# 6pin_bus.net
KiCad netlist of a schematic drawn in EAGLE
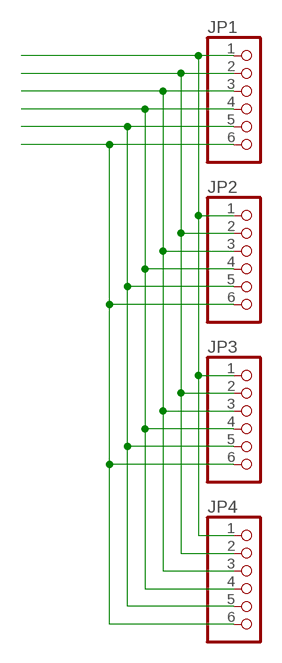
[diagram p0: schematic, sheet 1]

(export (version "E")
  (design (tool "Eeschema 10.0.6"))
  (components
    (comp (ref "JP1")
      (value "PINHD-1X6")
      (footprint "eagle-import:1X06")
      (libsource (lib "eagle-import") (part "PINHD-1X6"))
    )
    (comp (ref "JP2")
      (value "PINHD-1X6")
      (footprint "eagle-import:1X06")
      (libsource (lib "eagle-import") (part "PINHD-1X6"))
    )
    (comp (ref "JP3")
      (value "PINHD-1X6")
      (footprint "eagle-import:1X06")
      (libsource (lib "eagle-import") (part "PINHD-1X6"))
    )
    (comp (ref "JP4")
      (value "PINHD-1X6")
      (footprint "eagle-import:1X06")
      (libsource (lib "eagle-import") (part "PINHD-1X6"))
    )
  )
  (nets
    (net (code "1") (name "Net-(JP1-Pad1)") (class "Default")
      (node (ref "JP1") (pin "1") (pinfunction "1_1") (pintype "passive"))
      (node (ref "JP2") (pin "1") (pinfunction "1_1") (pintype "passive"))
      (node (ref "JP3") (pin "1") (pinfunction "1_1") (pintype "passive"))
      (node (ref "JP4") (pin "1") (pinfunction "1_1") (pintype "passive"))
    )
    (net (code "2") (name "Net-(JP1-Pad2)") (class "Default")
      (node (ref "JP1") (pin "2") (pinfunction "2_2") (pintype "passive"))
      (node (ref "JP2") (pin "2") (pinfunction "2_2") (pintype "passive"))
      (node (ref "JP3") (pin "2") (pinfunction "2_2") (pintype "passive"))
      (node (ref "JP4") (pin "2") (pinfunction "2_2") (pintype "passive"))
    )
    (net (code "3") (name "Net-(JP1-Pad3)") (class "Default")
      (node (ref "JP1") (pin "3") (pinfunction "3_3") (pintype "passive"))
      (node (ref "JP2") (pin "3") (pinfunction "3_3") (pintype "passive"))
      (node (ref "JP3") (pin "3") (pinfunction "3_3") (pintype "passive"))
      (node (ref "JP4") (pin "3") (pinfunction "3_3") (pintype "passive"))
    )
    (net (code "4") (name "Net-(JP1-Pad4)") (class "Default")
      (node (ref "JP1") (pin "4") (pinfunction "4_4") (pintype "passive"))
      (node (ref "JP2") (pin "4") (pinfunction "4_4") (pintype "passive"))
      (node (ref "JP3") (pin "4") (pinfunction "4_4") (pintype "passive"))
      (node (ref "JP4") (pin "4") (pinfunction "4_4") (pintype "passive"))
    )
    (net (code "5") (name "Net-(JP1-Pad5)") (class "Default")
      (node (ref "JP1") (pin "5") (pinfunction "5_5") (pintype "passive"))
      (node (ref "JP2") (pin "5") (pinfunction "5_5") (pintype "passive"))
      (node (ref "JP3") (pin "5") (pinfunction "5_5") (pintype "passive"))
      (node (ref "JP4") (pin "5") (pinfunction "5_5") (pintype "passive"))
    )
    (net (code "6") (name "Net-(JP1-Pad6)") (class "Default")
      (node (ref "JP1") (pin "6") (pinfunction "6_6") (pintype "passive"))
      (node (ref "JP2") (pin "6") (pinfunction "6_6") (pintype "passive"))
      (node (ref "JP3") (pin "6") (pinfunction "6_6") (pintype "passive"))
      (node (ref "JP4") (pin "6") (pinfunction "6_6") (pintype "passive"))
    )
  )
)
